# Supply.net
KiCad netlist of a schematic drawn in Altium Designer
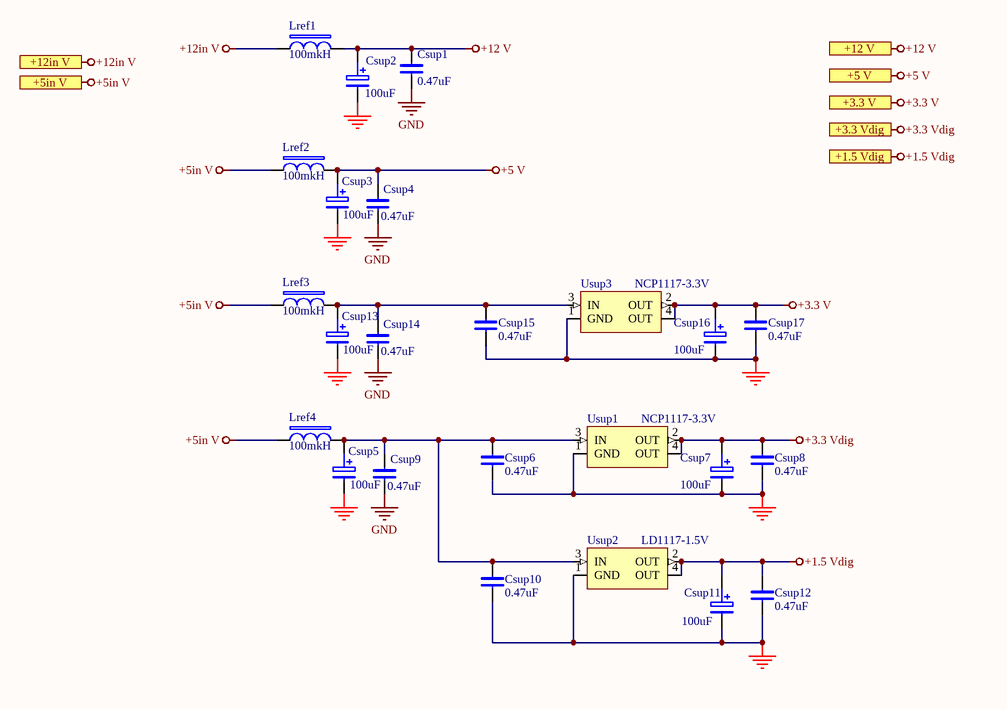
[diagram p0: Supply.SchDoc]

(export (version "E")
  (design (tool "Eeschema 10.0.6"))
  (components
    (comp (ref "Csup1") (value "0.47uF") (footprint "chip0805") (libsource (lib "*") (part "C")))
    (comp (ref "Csup2") (value "100uF") (footprint "CEL-SMD300") (libsource (lib "*") (part "C POL")))
    (comp (ref "Csup3") (value "100uF") (footprint "CEL-SMD300") (libsource (lib "*") (part "C POL")))
    (comp (ref "Csup4") (value "0.47uF") (footprint "chip0805") (libsource (lib "*") (part "C")))
    (comp (ref "Csup5") (value "100uF") (footprint "CEL-SMD300") (libsource (lib "*") (part "C POL")))
    (comp (ref "Csup6") (value "0.47uF") (footprint "chip0805") (libsource (lib "*") (part "C")))
    (comp (ref "Csup7") (value "100uF") (footprint "CEL-SMD300") (libsource (lib "*") (part "C POL")))
    (comp (ref "Csup8") (value "0.47uF") (footprint "chip0805") (libsource (lib "*") (part "C")))
    (comp (ref "Csup9") (value "0.47uF") (footprint "chip0805") (libsource (lib "*") (part "C")))
    (comp (ref "Csup10") (value "0.47uF") (footprint "chip0805") (libsource (lib "*") (part "C")))
    (comp (ref "Csup11") (value "100uF") (footprint "CEL-SMD300") (libsource (lib "*") (part "C POL")))
    (comp (ref "Csup12") (value "0.47uF") (footprint "chip0805") (libsource (lib "*") (part "C")))
    (comp (ref "Csup13") (value "100uF") (footprint "CEL-SMD300") (libsource (lib "*") (part "C POL")))
    (comp (ref "Csup14") (value "0.47uF") (footprint "chip0805") (libsource (lib "*") (part "C")))
    (comp (ref "Csup15") (value "0.47uF") (footprint "chip0805") (libsource (lib "*") (part "C")))
    (comp (ref "Csup16") (value "100uF") (footprint "CEL-SMD300") (libsource (lib "*") (part "C POL")))
    (comp (ref "Csup17") (value "0.47uF") (footprint "chip0805") (libsource (lib "*") (part "C")))
    (comp (ref "Lref1") (value "100mkH") (footprint "SDR0604") (libsource (lib "*") (part "DR")))
    (comp (ref "Lref2") (value "100mkH") (footprint "SDR0604") (libsource (lib "*") (part "DR")))
    (comp (ref "Lref3") (value "100mkH") (footprint "SDR0604") (libsource (lib "*") (part "DR")))
    (comp (ref "Lref4") (value "100mkH") (footprint "SDR0604") (libsource (lib "*") (part "DR")))
    (comp (ref "Usup1")
      (value "NCP1117-3.3V")
      (footprint "TO-252")
      (libsource (lib "vAnalog") (part "NCP1117-3.3V"))
    )
    (comp (ref "Usup2")
      (value "LD1117-1.5V")
      (footprint "TO-252")
      (libsource (lib "vAnalog") (part "NCP1117-3.3V"))
    )
    (comp (ref "Usup3")
      (value "NCP1117-3.3V")
      (footprint "TO-252")
      (libsource (lib "vAnalog") (part "NCP1117-3.3V"))
    )
  )
  (nets
    (net (code "1") (name "+1.5 Vdig") (class "Default")
      (node (ref "Csup11") (pin "+") (pinfunction "+_+") (pintype "passive"))
      (node (ref "Csup12") (pin "1") (pinfunction "1_1") (pintype "passive"))
      (node (ref "Usup2") (pin "2") (pinfunction "OUT_2") (pintype "output"))
      (node (ref "Usup2") (pin "4") (pinfunction "OUT_4") (pintype "passive"))
    )
    (net (code "2") (name "+3.3 V") (class "Default")
      (node (ref "Csup16") (pin "+") (pinfunction "+_+") (pintype "passive"))
      (node (ref "Csup17") (pin "1") (pinfunction "1_1") (pintype "passive"))
      (node (ref "Usup3") (pin "2") (pinfunction "OUT_2") (pintype "output"))
      (node (ref "Usup3") (pin "4") (pinfunction "OUT_4") (pintype "passive"))
    )
    (net (code "3") (name "+3.3 Vdig") (class "Default")
      (node (ref "Csup7") (pin "+") (pinfunction "+_+") (pintype "passive"))
      (node (ref "Csup8") (pin "1") (pinfunction "1_1") (pintype "passive"))
      (node (ref "Usup1") (pin "2") (pinfunction "OUT_2") (pintype "output"))
      (node (ref "Usup1") (pin "4") (pinfunction "OUT_4") (pintype "passive"))
    )
    (net (code "4") (name "+5 V") (class "Default")
      (node (ref "Csup3") (pin "+") (pinfunction "+_+") (pintype "passive"))
      (node (ref "Csup4") (pin "1") (pinfunction "1_1") (pintype "passive"))
      (node (ref "Lref2") (pin "2") (pinfunction "2_2") (pintype "passive"))
    )
    (net (code "5") (name "+5in V") (class "Default")
      (node (ref "Lref2") (pin "1") (pinfunction "1_1") (pintype "passive"))
      (node (ref "Lref3") (pin "1") (pinfunction "1_1") (pintype "passive"))
      (node (ref "Lref4") (pin "1") (pinfunction "1_1") (pintype "passive"))
    )
    (net (code "6") (name "+12 V") (class "Default")
      (node (ref "Csup1") (pin "1") (pinfunction "1_1") (pintype "passive"))
      (node (ref "Csup2") (pin "+") (pinfunction "+_+") (pintype "passive"))
      (node (ref "Lref1") (pin "2") (pinfunction "2_2") (pintype "passive"))
    )
    (net (code "7") (name "+12in V") (class "Default")
      (node (ref "Lref1") (pin "1") (pinfunction "1_1") (pintype "passive"))
    )
    (net (code "8") (name "GND") (class "Default")
      (node (ref "Csup1") (pin "2") (pinfunction "2_2") (pintype "passive"))
      (node (ref "Csup10") (pin "2") (pinfunction "2_2") (pintype "passive"))
      (node (ref "Csup11") (pin "-") (pinfunction "-_-") (pintype "passive"))
      (node (ref "Csup12") (pin "2") (pinfunction "2_2") (pintype "passive"))
      (node (ref "Csup13") (pin "-") (pinfunction "-_-") (pintype "passive"))
      (node (ref "Csup14") (pin "2") (pinfunction "2_2") (pintype "passive"))
      (node (ref "Csup15") (pin "2") (pinfunction "2_2") (pintype "passive"))
      (node (ref "Csup16") (pin "-") (pinfunction "-_-") (pintype "passive"))
      (node (ref "Csup17") (pin "2") (pinfunction "2_2") (pintype "passive"))
      (node (ref "Csup2") (pin "-") (pinfunction "-_-") (pintype "passive"))
      (node (ref "Csup3") (pin "-") (pinfunction "-_-") (pintype "passive"))
      (node (ref "Csup4") (pin "2") (pinfunction "2_2") (pintype "passive"))
      (node (ref "Csup5") (pin "-") (pinfunction "-_-") (pintype "passive"))
      (node (ref "Csup6") (pin "2") (pinfunction "2_2") (pintype "passive"))
      (node (ref "Csup7") (pin "-") (pinfunction "-_-") (pintype "passive"))
      (node (ref "Csup8") (pin "2") (pinfunction "2_2") (pintype "passive"))
      (node (ref "Csup9") (pin "2") (pinfunction "2_2") (pintype "passive"))
      (node (ref "Usup1") (pin "1") (pinfunction "GND_1") (pintype "power_in"))
      (node (ref "Usup2") (pin "1") (pinfunction "GND_1") (pintype "power_in"))
      (node (ref "Usup3") (pin "1") (pinfunction "GND_1") (pintype "power_in"))
    )
    (net (code "9") (name "Net-(Usup1-IN)") (class "Default")
      (node (ref "Csup10") (pin "1") (pinfunction "1_1") (pintype "passive"))
      (node (ref "Csup5") (pin "+") (pinfunction "+_+") (pintype "passive"))
      (node (ref "Csup6") (pin "1") (pinfunction "1_1") (pintype "passive"))
      (node (ref "Csup9") (pin "1") (pinfunction "1_1") (pintype "passive"))
      (node (ref "Lref4") (pin "2") (pinfunction "2_2") (pintype "passive"))
      (node (ref "Usup1") (pin "3") (pinfunction "IN_3") (pintype "input"))
      (node (ref "Usup2") (pin "3") (pinfunction "IN_3") (pintype "input"))
    )
    (net (code "10") (name "Net-(Usup3-IN)") (class "Default")
      (node (ref "Csup13") (pin "+") (pinfunction "+_+") (pintype "passive"))
      (node (ref "Csup14") (pin "1") (pinfunction "1_1") (pintype "passive"))
      (node (ref "Csup15") (pin "1") (pinfunction "1_1") (pintype "passive"))
      (node (ref "Lref3") (pin "2") (pinfunction "2_2") (pintype "passive"))
      (node (ref "Usup3") (pin "3") (pinfunction "IN_3") (pintype "input"))
    )
  )
)
